# ADC2.net
KiCad netlist of a schematic drawn in Altium Designer
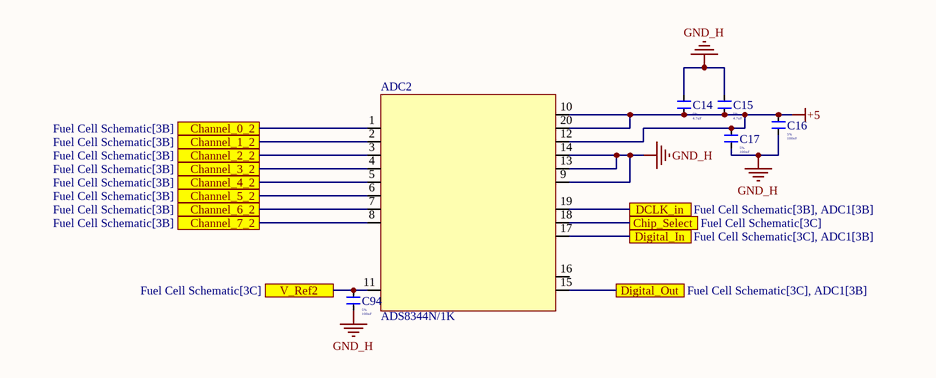
[diagram p0: ADC2.SchDoc]

(export (version "E")
  (design (tool "Eeschema 10.0.6"))
  (components
    (comp (ref "ADC2")
      (value "ADS8344N/1K")
      (footprint "ADS8344")
      (description "IC ADC 16BIT SAR 20SSOP")
      (fields (field (name "MANUFACTURER") "Texas Instruments"))
      (libsource (lib "Schlib1") (part "ADS8344N/1K"))
    )
    (comp (ref "C14")
      (value "~")
      (footprint "Capacitor_Kemet_0805")
      (description "CAP CER 4.7UF 16V X7R 0805")
      (fields
        (field (name "MANUFACTURER") "KEMET")
        (field (name "MANUFACTURER PART NUMBER") "C0805C475J4RACAUTO")
        (field (name "TOLERANCE") "5%")
        (field (name "CAPACITANCE") "4.7uF")
      )
      (libsource (lib "Schlib1") (part "C0805C475J4RACAUTO"))
    )
    (comp (ref "C15")
      (value "~")
      (footprint "Capacitor_Kemet_0805")
      (description "CAP CER 4.7UF 16V X7R 0805")
      (fields
        (field (name "MANUFACTURER") "KEMET")
        (field (name "MANUFACTURER PART NUMBER") "C0805C475J4RACAUTO")
        (field (name "TOLERANCE") "5%")
        (field (name "CAPACITANCE") "4.7uF")
      )
      (libsource (lib "Schlib1") (part "C0805C475J4RACAUTO"))
    )
    (comp (ref "C16")
      (value "~")
      (footprint "Capacitor_Kemet_0805")
      (description "Cap Ceramic 0.1uF 16V X7R 5% SMD 0805 125°C Plastic T/R")
      (fields
        (field (name "MANUFACTURER") "KEMET")
        (field (name "MANUFACTURER PART NUMBER") "C0805C104J4RACTU")
        (field (name "DISSIPATION FACTOR") "5%")
        (field (name "CAPACITANCE") "100nF")
      )
      (libsource (lib "Schlib1") (part "C0805C104J4RACTU"))
    )
    (comp (ref "C17")
      (value "~")
      (footprint "Capacitor_Kemet_0805")
      (description "Cap Ceramic 0.1uF 16V X7R 5% SMD 0805 125°C Plastic T/R")
      (fields
        (field (name "MANUFACTURER") "KEMET")
        (field (name "MANUFACTURER PART NUMBER") "C0805C104J4RACTU")
        (field (name "DISSIPATION FACTOR") "5%")
        (field (name "CAPACITANCE") "100nF")
      )
      (libsource (lib "Schlib1") (part "C0805C104J4RACTU"))
    )
    (comp (ref "C94")
      (value "~")
      (footprint "Capacitor_Kemet_0805")
      (description "Cap Ceramic 0.1uF 16V X7R 5% SMD 0805 125°C Plastic T/R")
      (fields
        (field (name "MANUFACTURER") "KEMET")
        (field (name "MANUFACTURER PART NUMBER") "C0805C104J4RACTU")
        (field (name "DISSIPATION FACTOR") "5%")
        (field (name "CAPACITANCE") "100nF")
      )
      (libsource (lib "Schlib1") (part "C0805C104J4RACTU"))
    )
  )
  (nets
    (net (code "1") (name "+5") (class "Default")
      (node (ref "ADC2") (pin "10") (pinfunction "Shutdown_10") (pintype "passive"))
      (node (ref "ADC2") (pin "12") (pinfunction "+VCC_12") (pintype "passive"))
      (node (ref "ADC2") (pin "20") (pinfunction "+VCC_20") (pintype "passive"))
      (node (ref "C14") (pin "1") (pinfunction "1_1") (pintype "passive"))
      (node (ref "C15") (pin "1") (pinfunction "1_1") (pintype "passive"))
      (node (ref "C16") (pin "2") (pinfunction "2_2") (pintype "passive"))
      (node (ref "C17") (pin "2") (pinfunction "2_2") (pintype "passive"))
    )
    (net (code "2") (name "/Channel_0_2") (class "Default")
      (node (ref "ADC2") (pin "1") (pinfunction "Channel_0_1") (pintype "passive"))
    )
    (net (code "3") (name "/Channel_1_2") (class "Default")
      (node (ref "ADC2") (pin "2") (pinfunction "Channel_1_2") (pintype "passive"))
    )
    (net (code "4") (name "/Channel_2_2") (class "Default")
      (node (ref "ADC2") (pin "3") (pinfunction "Channel_2_3") (pintype "passive"))
    )
    (net (code "5") (name "/Channel_3_2") (class "Default")
      (node (ref "ADC2") (pin "4") (pinfunction "Channel_3_4") (pintype "passive"))
    )
    (net (code "6") (name "/Channel_4_2") (class "Default")
      (node (ref "ADC2") (pin "5") (pinfunction "Channel_4_5") (pintype "passive"))
    )
    (net (code "7") (name "/Channel_5_2") (class "Default")
      (node (ref "ADC2") (pin "6") (pinfunction "Channel_5_6") (pintype "passive"))
    )
    (net (code "8") (name "/Channel_6_2") (class "Default")
      (node (ref "ADC2") (pin "7") (pinfunction "Channel_6_7") (pintype "passive"))
    )
    (net (code "9") (name "/Channel_7_2") (class "Default")
      (node (ref "ADC2") (pin "8") (pinfunction "Channel_7_8") (pintype "passive"))
    )
    (net (code "10") (name "/Chip_Select") (class "Default")
      (node (ref "ADC2") (pin "18") (pinfunction "Chip_Select_18") (pintype "passive"))
    )
    (net (code "11") (name "/DCLK_in") (class "Default")
      (node (ref "ADC2") (pin "19") (pinfunction "Digital_Clock_19") (pintype "passive"))
    )
    (net (code "12") (name "/Digital_In") (class "Default")
      (node (ref "ADC2") (pin "17") (pinfunction "Digital_In_17") (pintype "passive"))
    )
    (net (code "13") (name "/Digital_Out") (class "Default")
      (node (ref "ADC2") (pin "15") (pinfunction "Digital_Out_15") (pintype "passive"))
    )
    (net (code "14") (name "/V_Ref2") (class "Default")
      (node (ref "ADC2") (pin "11") (pinfunction "V_Reference_11") (pintype "passive"))
      (node (ref "C94") (pin "2") (pinfunction "2_2") (pintype "passive"))
    )
    (net (code "15") (name "GND_H") (class "Default")
      (node (ref "ADC2") (pin "13") (pinfunction "Ground_13") (pintype "passive"))
      (node (ref "ADC2") (pin "14") (pinfunction "Ground_14") (pintype "passive"))
      (node (ref "ADC2") (pin "9") (pinfunction "Common_Reference_9") (pintype "passive"))
      (node (ref "C14") (pin "2") (pinfunction "2_2") (pintype "passive"))
      (node (ref "C15") (pin "2") (pinfunction "2_2") (pintype "passive"))
      (node (ref "C16") (pin "1") (pinfunction "1_1") (pintype "passive"))
      (node (ref "C17") (pin "1") (pinfunction "1_1") (pintype "passive"))
      (node (ref "C94") (pin "1") (pinfunction "1_1") (pintype "passive"))
    )
    (net (code "16") (name "unconnected-(ADC2-Busy-Pad16)") (class "Default")
      (node (ref "ADC2") (pin "16") (pinfunction "Busy_16") (pintype "passive"))
    )
  )
)
